# Rocket4Narrow.net
KiCad netlist of a schematic drawn in EAGLE
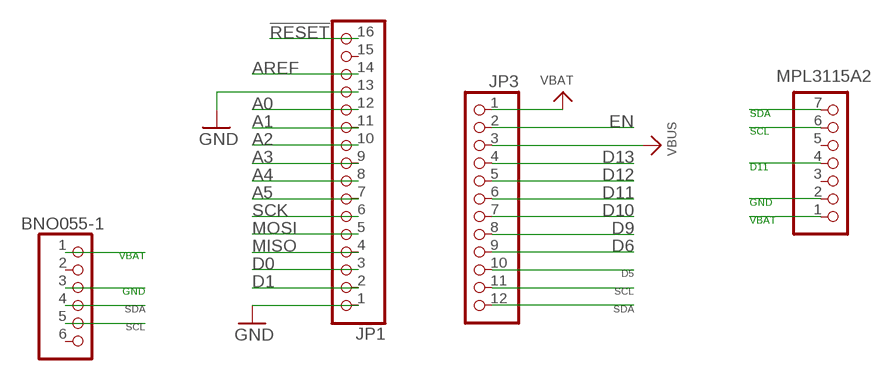
[diagram p0: schematic, sheet 1]

(export (version "E")
  (design (tool "Eeschema 10.0.6"))
  (components
    (comp (ref "BNO055-1")
      (value "HEADER-1X670MIL")
      (footprint "eagle-import:1X06_ROUND_70")
      (libsource (lib "eagle-import") (part "HEADER-1X670MIL"))
    )
    (comp (ref "JP1")
      (value "HEADER-1X16ROUND")
      (footprint "eagle-import:1X16_ROUND")
      (libsource (lib "eagle-import") (part "HEADER-1X16ROUND"))
    )
    (comp (ref "JP3")
      (value "HEADER-1X12")
      (footprint "eagle-import:1X12_ROUND")
      (libsource (lib "eagle-import") (part "HEADER-1X12"))
    )
    (comp (ref "MPL3115A2")
      (value "HEADER-1X770MIL")
      (footprint "eagle-import:1X07_ROUND_70")
      (libsource (lib "eagle-import") (part "HEADER-1X770MIL"))
    )
  )
  (nets
    (net (code "1") (name "/A0") (class "Default")
      (node (ref "JP1") (pin "12") (pinfunction "12_12") (pintype "passive"))
    )
    (net (code "2") (name "/A1") (class "Default")
      (node (ref "JP1") (pin "11") (pinfunction "11_11") (pintype "passive"))
    )
    (net (code "3") (name "/A2") (class "Default")
      (node (ref "JP1") (pin "10") (pinfunction "10_10") (pintype "passive"))
    )
    (net (code "4") (name "/A3") (class "Default")
      (node (ref "JP1") (pin "9") (pinfunction "9_9") (pintype "passive"))
    )
    (net (code "5") (name "/A4") (class "Default")
      (node (ref "JP1") (pin "8") (pinfunction "8_8") (pintype "passive"))
    )
    (net (code "6") (name "/A5") (class "Default")
      (node (ref "JP1") (pin "7") (pinfunction "7_7") (pintype "passive"))
    )
    (net (code "7") (name "/AREF") (class "Default")
      (node (ref "JP1") (pin "14") (pinfunction "14_14") (pintype "passive"))
    )
    (net (code "8") (name "/D0") (class "Default")
      (node (ref "JP1") (pin "3") (pinfunction "3_3") (pintype "passive"))
    )
    (net (code "9") (name "/D1") (class "Default")
      (node (ref "JP1") (pin "2") (pinfunction "2_2") (pintype "passive"))
    )
    (net (code "10") (name "/D5") (class "Default")
      (node (ref "JP3") (pin "10") (pinfunction "10_10") (pintype "passive"))
    )
    (net (code "11") (name "/D6") (class "Default")
      (node (ref "JP3") (pin "9") (pinfunction "9_9") (pintype "passive"))
    )
    (net (code "12") (name "/D9") (class "Default")
      (node (ref "JP3") (pin "8") (pinfunction "8_8") (pintype "passive"))
    )
    (net (code "13") (name "/D10") (class "Default")
      (node (ref "JP3") (pin "7") (pinfunction "7_7") (pintype "passive"))
    )
    (net (code "14") (name "/D11") (class "Default")
      (node (ref "JP3") (pin "6") (pinfunction "6_6") (pintype "passive"))
      (node (ref "MPL3115A2") (pin "4") (pinfunction "4_4") (pintype "passive"))
    )
    (net (code "15") (name "/D12") (class "Default")
      (node (ref "JP3") (pin "5") (pinfunction "5_5") (pintype "passive"))
    )
    (net (code "16") (name "/D13") (class "Default")
      (node (ref "JP3") (pin "4") (pinfunction "4_4") (pintype "passive"))
    )
    (net (code "17") (name "/EN") (class "Default")
      (node (ref "JP3") (pin "2") (pinfunction "2_2") (pintype "passive"))
    )
    (net (code "18") (name "/MISO") (class "Default")
      (node (ref "JP1") (pin "4") (pinfunction "4_4") (pintype "passive"))
    )
    (net (code "19") (name "/MOSI") (class "Default")
      (node (ref "JP1") (pin "5") (pinfunction "5_5") (pintype "passive"))
    )
    (net (code "20") (name "/SCK") (class "Default")
      (node (ref "JP1") (pin "6") (pinfunction "6_6") (pintype "passive"))
    )
    (net (code "21") (name "/SCL") (class "Default")
      (node (ref "BNO055-1") (pin "5") (pinfunction "5_5") (pintype "passive"))
      (node (ref "JP3") (pin "11") (pinfunction "11_11") (pintype "passive"))
      (node (ref "MPL3115A2") (pin "6") (pinfunction "6_6") (pintype "passive"))
    )
    (net (code "22") (name "/SDA") (class "Default")
      (node (ref "BNO055-1") (pin "4") (pinfunction "4_4") (pintype "passive"))
      (node (ref "JP3") (pin "12") (pinfunction "12_12") (pintype "passive"))
      (node (ref "MPL3115A2") (pin "7") (pinfunction "7_7") (pintype "passive"))
    )
    (net (code "23") (name "/~{RESET}") (class "Default")
      (node (ref "JP1") (pin "16") (pinfunction "16_16") (pintype "passive"))
    )
    (net (code "24") (name "GND") (class "Default")
      (node (ref "BNO055-1") (pin "3") (pinfunction "3_3") (pintype "passive"))
      (node (ref "JP1") (pin "1") (pinfunction "1_1") (pintype "passive"))
      (node (ref "JP1") (pin "13") (pinfunction "13_13") (pintype "passive"))
      (node (ref "MPL3115A2") (pin "2") (pinfunction "2_2") (pintype "passive"))
    )
    (net (code "25") (name "VBAT") (class "Default")
      (node (ref "BNO055-1") (pin "1") (pinfunction "1_1") (pintype "passive"))
      (node (ref "JP3") (pin "1") (pinfunction "1_1") (pintype "passive"))
      (node (ref "MPL3115A2") (pin "1") (pinfunction "1_1") (pintype "passive"))
    )
    (net (code "26") (name "VBUS") (class "Default")
      (node (ref "JP3") (pin "3") (pinfunction "3_3") (pintype "passive"))
    )
    (net (code "27") (name "unconnected-(BNO055-1-Pad2)") (class "Default")
      (node (ref "BNO055-1") (pin "2") (pinfunction "2_2") (pintype "passive"))
    )
    (net (code "28") (name "unconnected-(BNO055-1-Pad6)") (class "Default")
      (node (ref "BNO055-1") (pin "6") (pinfunction "6_6") (pintype "passive"))
    )
    (net (code "29") (name "unconnected-(JP1-Pad15)") (class "Default")
      (node (ref "JP1") (pin "15") (pinfunction "15_15") (pintype "passive"))
    )
    (net (code "30") (name "unconnected-(MPL3115A2-Pad3)") (class "Default")
      (node (ref "MPL3115A2") (pin "3") (pinfunction "3_3") (pintype "passive"))
    )
    (net (code "31") (name "unconnected-(MPL3115A2-Pad5)") (class "Default")
      (node (ref "MPL3115A2") (pin "5") (pinfunction "5_5") (pintype "passive"))
    )
  )
)
